# RG-RGB-Encoder-v10.net
KiCad netlist of a schematic drawn in EAGLE
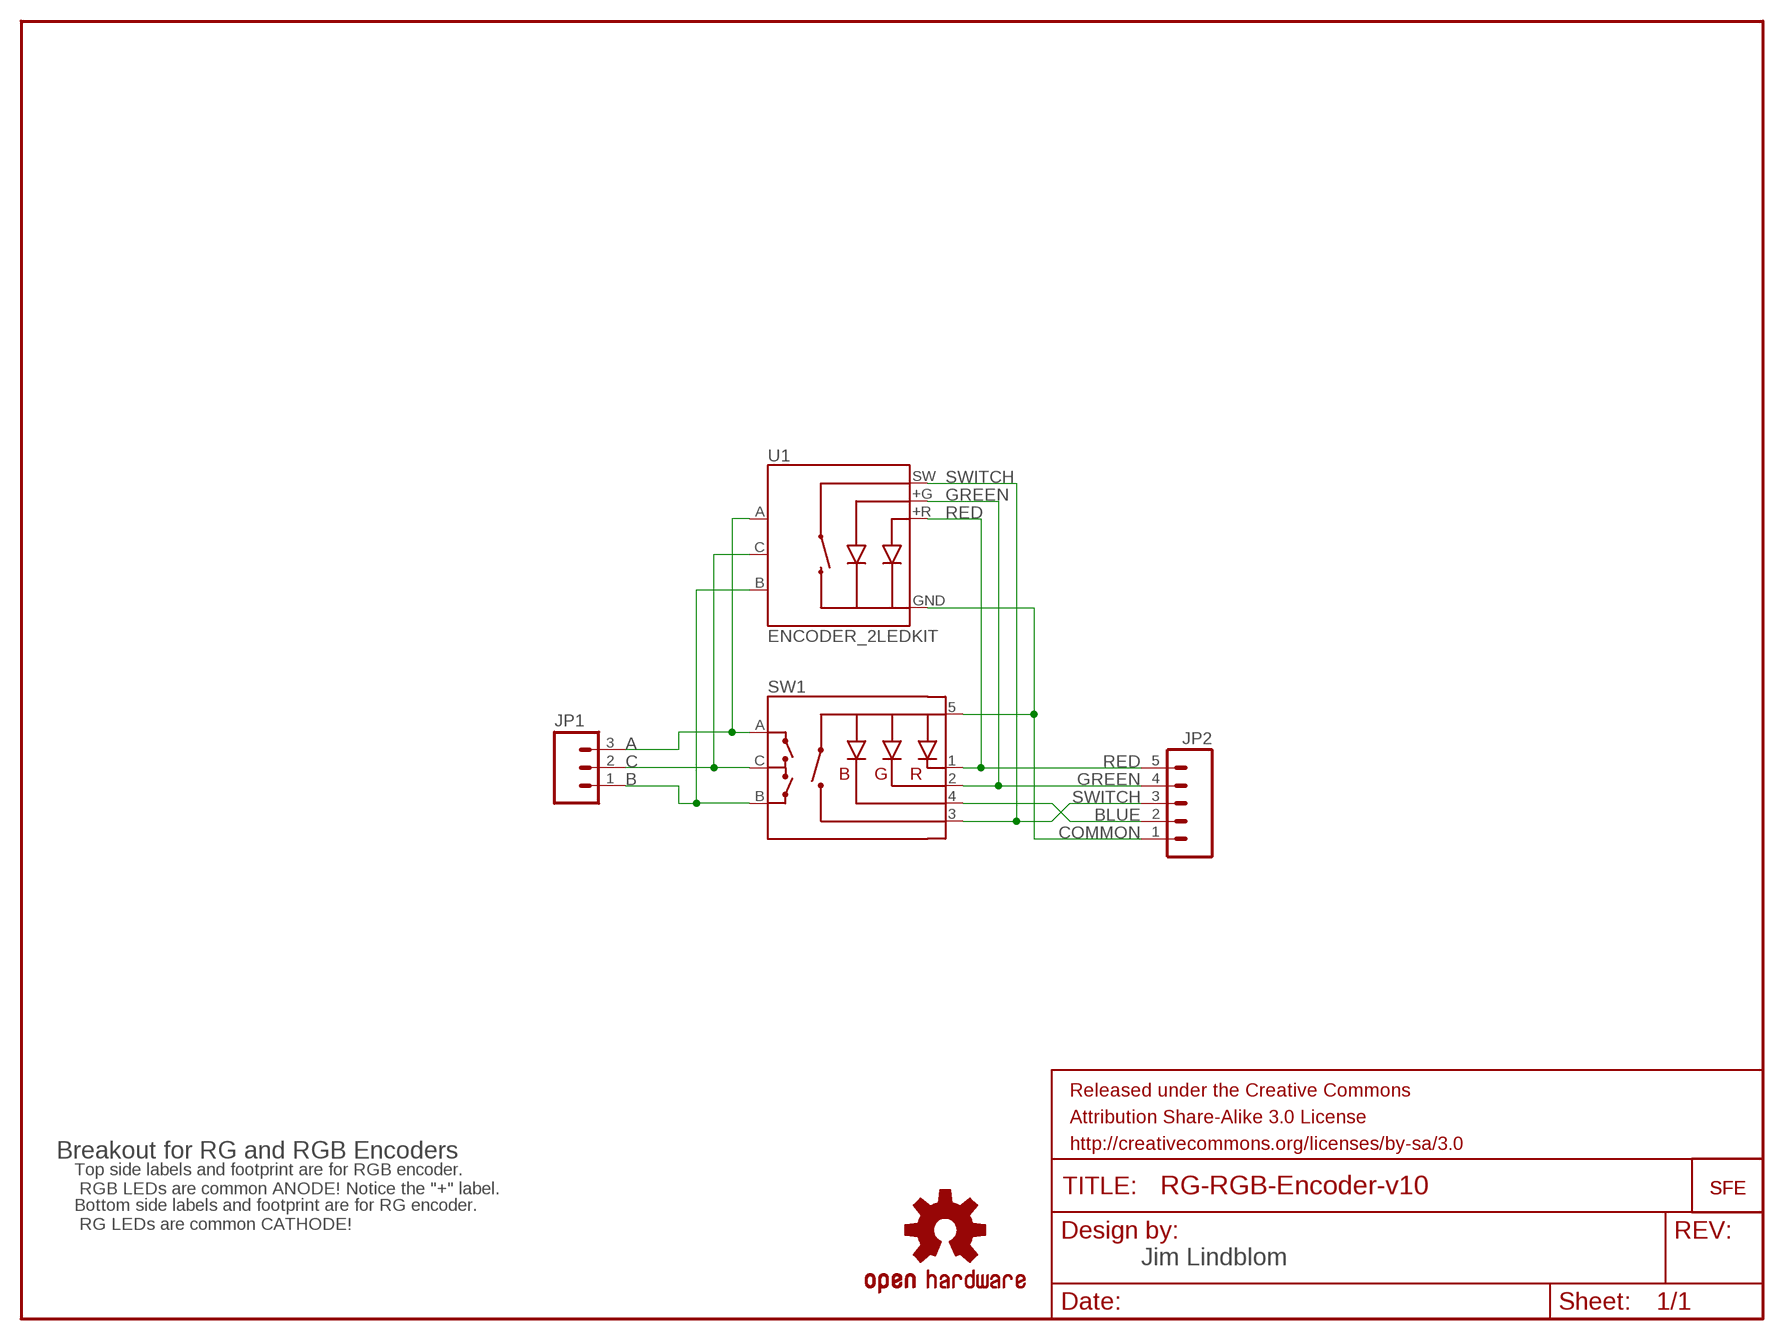
[diagram p0: schematic, sheet 1]

(export (version "E")
  (design (tool "Eeschema 10.0.6"))
  (components
    (comp (ref "FRAME1")
      (value "FRAME-LETTER")
      (footprint "eagle-import:CREATIVE_COMMONS")
      (libsource (lib "eagle-import") (part "FRAME-LETTER"))
    )
    (comp (ref "JP1")
      (value "M03PTH")
      (footprint "eagle-import:1X03")
      (libsource (lib "eagle-import") (part "M03PTH"))
    )
    (comp (ref "JP2")
      (value "M05PTH")
      (footprint "eagle-import:1X05")
      (libsource (lib "eagle-import") (part "M05PTH"))
    )
    (comp (ref "JP3")
      (value "LOGO-SFESK")
      (footprint "eagle-import:SFE-LOGO-FLAME")
      (libsource (lib "eagle-import") (part "LOGO-SFESK"))
    )
    (comp (ref "JP4")
      (value "LOGO-SFESK")
      (footprint "eagle-import:SFE-LOGO-FLAME")
      (libsource (lib "eagle-import") (part "LOGO-SFESK"))
    )
    (comp (ref "SW1")
      (value "ENCODER_RGB_CAKIT")
      (footprint "eagle-import:ENCODER_LED_3_KIT")
      (libsource (lib "eagle-import") (part "ENCODER_RGB_CAKIT"))
    )
    (comp (ref "U$2")
      (value "OSHW-LOGOS")
      (footprint "eagle-import:OSHW-LOGO-S")
      (libsource (lib "eagle-import") (part "OSHW-LOGOS"))
    )
    (comp (ref "U1")
      (value "ENCODER_2LEDKIT")
      (footprint "eagle-import:ENCODER_LED_2_KIT")
      (libsource (lib "eagle-import") (part "ENCODER_2LEDKIT"))
    )
  )
  (nets
    (net (code "1") (name "/A") (class "Default")
      (node (ref "JP1") (pin "3") (pinfunction "3_3") (pintype "passive"))
      (node (ref "SW1") (pin "A") (pinfunction "A_A") (pintype "bidirectional"))
      (node (ref "U1") (pin "A") (pinfunction "A_A") (pintype "bidirectional"))
    )
    (net (code "2") (name "/B") (class "Default")
      (node (ref "JP1") (pin "1") (pinfunction "1_1") (pintype "passive"))
      (node (ref "SW1") (pin "B") (pinfunction "B_B") (pintype "bidirectional"))
      (node (ref "U1") (pin "B") (pinfunction "B_B") (pintype "bidirectional"))
    )
    (net (code "3") (name "/BLUE") (class "Default")
      (node (ref "JP2") (pin "2") (pinfunction "2_2") (pintype "passive"))
      (node (ref "SW1") (pin "4") (pinfunction "-B_4") (pintype "passive"))
    )
    (net (code "4") (name "/C") (class "Default")
      (node (ref "JP1") (pin "2") (pinfunction "2_2") (pintype "passive"))
      (node (ref "SW1") (pin "C") (pinfunction "C_C") (pintype "bidirectional"))
      (node (ref "U1") (pin "C") (pinfunction "C_C") (pintype "bidirectional"))
    )
    (net (code "5") (name "/COMMON") (class "Default")
      (node (ref "JP2") (pin "1") (pinfunction "1_1") (pintype "passive"))
      (node (ref "SW1") (pin "5") (pinfunction "+_5") (pintype "passive"))
      (node (ref "U1") (pin "GND") (pinfunction "-_GND") (pintype "passive"))
    )
    (net (code "6") (name "/GREEN") (class "Default")
      (node (ref "JP2") (pin "4") (pinfunction "4_4") (pintype "passive"))
      (node (ref "SW1") (pin "2") (pinfunction "-G_2") (pintype "passive"))
      (node (ref "U1") (pin "+G") (pinfunction "+G_+G") (pintype "passive"))
    )
    (net (code "7") (name "/RED") (class "Default")
      (node (ref "JP2") (pin "5") (pinfunction "5_5") (pintype "passive"))
      (node (ref "SW1") (pin "1") (pinfunction "-R_1") (pintype "passive"))
      (node (ref "U1") (pin "+R") (pinfunction "+R_+R") (pintype "passive"))
    )
    (net (code "8") (name "/SWITCH") (class "Default")
      (node (ref "JP2") (pin "3") (pinfunction "3_3") (pintype "passive"))
      (node (ref "SW1") (pin "3") (pinfunction "SW_3") (pintype "passive"))
      (node (ref "U1") (pin "SW") (pinfunction "SW_SW") (pintype "passive"))
    )
  )
)
